# prog.net
KiCad netlist of a schematic drawn in Altium Designer
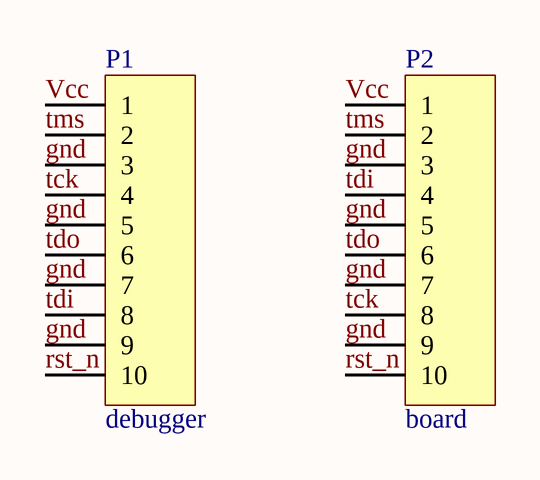
[diagram p0: prog.SchDoc]

(export (version "E")
  (design (tool "Eeschema 10.0.6"))
  (components
    (comp (ref "P1")
      (value "debugger")
      (footprint "HDR1X10")
      (description "Header, 10-Pin")
      (fields (field (name "PUBLISHER") "Altium Limited"))
      (libsource (lib "Miscellaneous Connectors") (part "Header 10"))
    )
    (comp (ref "P2")
      (value "board")
      (footprint "HDR1X10")
      (description "Header, 10-Pin")
      (fields (field (name "PUBLISHER") "Altium Limited"))
      (libsource (lib "Miscellaneous Connectors") (part "Header 10"))
    )
  )
  (nets
    (net (code "1") (name "/Vcc") (class "Default")
      (node (ref "P1") (pin "1") (pinfunction "1_1") (pintype "passive"))
      (node (ref "P2") (pin "1") (pinfunction "1_1") (pintype "passive"))
    )
    (net (code "2") (name "/gnd") (class "Default")
      (node (ref "P1") (pin "3") (pinfunction "3_3") (pintype "passive"))
      (node (ref "P1") (pin "5") (pinfunction "5_5") (pintype "passive"))
      (node (ref "P1") (pin "7") (pinfunction "7_7") (pintype "passive"))
      (node (ref "P1") (pin "9") (pinfunction "9_9") (pintype "passive"))
      (node (ref "P2") (pin "3") (pinfunction "3_3") (pintype "passive"))
      (node (ref "P2") (pin "5") (pinfunction "5_5") (pintype "passive"))
      (node (ref "P2") (pin "7") (pinfunction "7_7") (pintype "passive"))
      (node (ref "P2") (pin "9") (pinfunction "9_9") (pintype "passive"))
    )
    (net (code "3") (name "/rst_n") (class "Default")
      (node (ref "P1") (pin "10") (pinfunction "10_10") (pintype "passive"))
      (node (ref "P2") (pin "10") (pinfunction "10_10") (pintype "passive"))
    )
    (net (code "4") (name "/tck") (class "Default")
      (node (ref "P1") (pin "4") (pinfunction "4_4") (pintype "passive"))
      (node (ref "P2") (pin "8") (pinfunction "8_8") (pintype "passive"))
    )
    (net (code "5") (name "/tdi") (class "Default")
      (node (ref "P1") (pin "8") (pinfunction "8_8") (pintype "passive"))
      (node (ref "P2") (pin "4") (pinfunction "4_4") (pintype "passive"))
    )
    (net (code "6") (name "/tdo") (class "Default")
      (node (ref "P1") (pin "6") (pinfunction "6_6") (pintype "passive"))
      (node (ref "P2") (pin "6") (pinfunction "6_6") (pintype "passive"))
    )
    (net (code "7") (name "/tms") (class "Default")
      (node (ref "P1") (pin "2") (pinfunction "2_2") (pintype "passive"))
      (node (ref "P2") (pin "2") (pinfunction "2_2") (pintype "passive"))
    )
  )
)
